# DRIVER_LED_AFE.net
KiCad netlist of a schematic drawn in Altium Designer
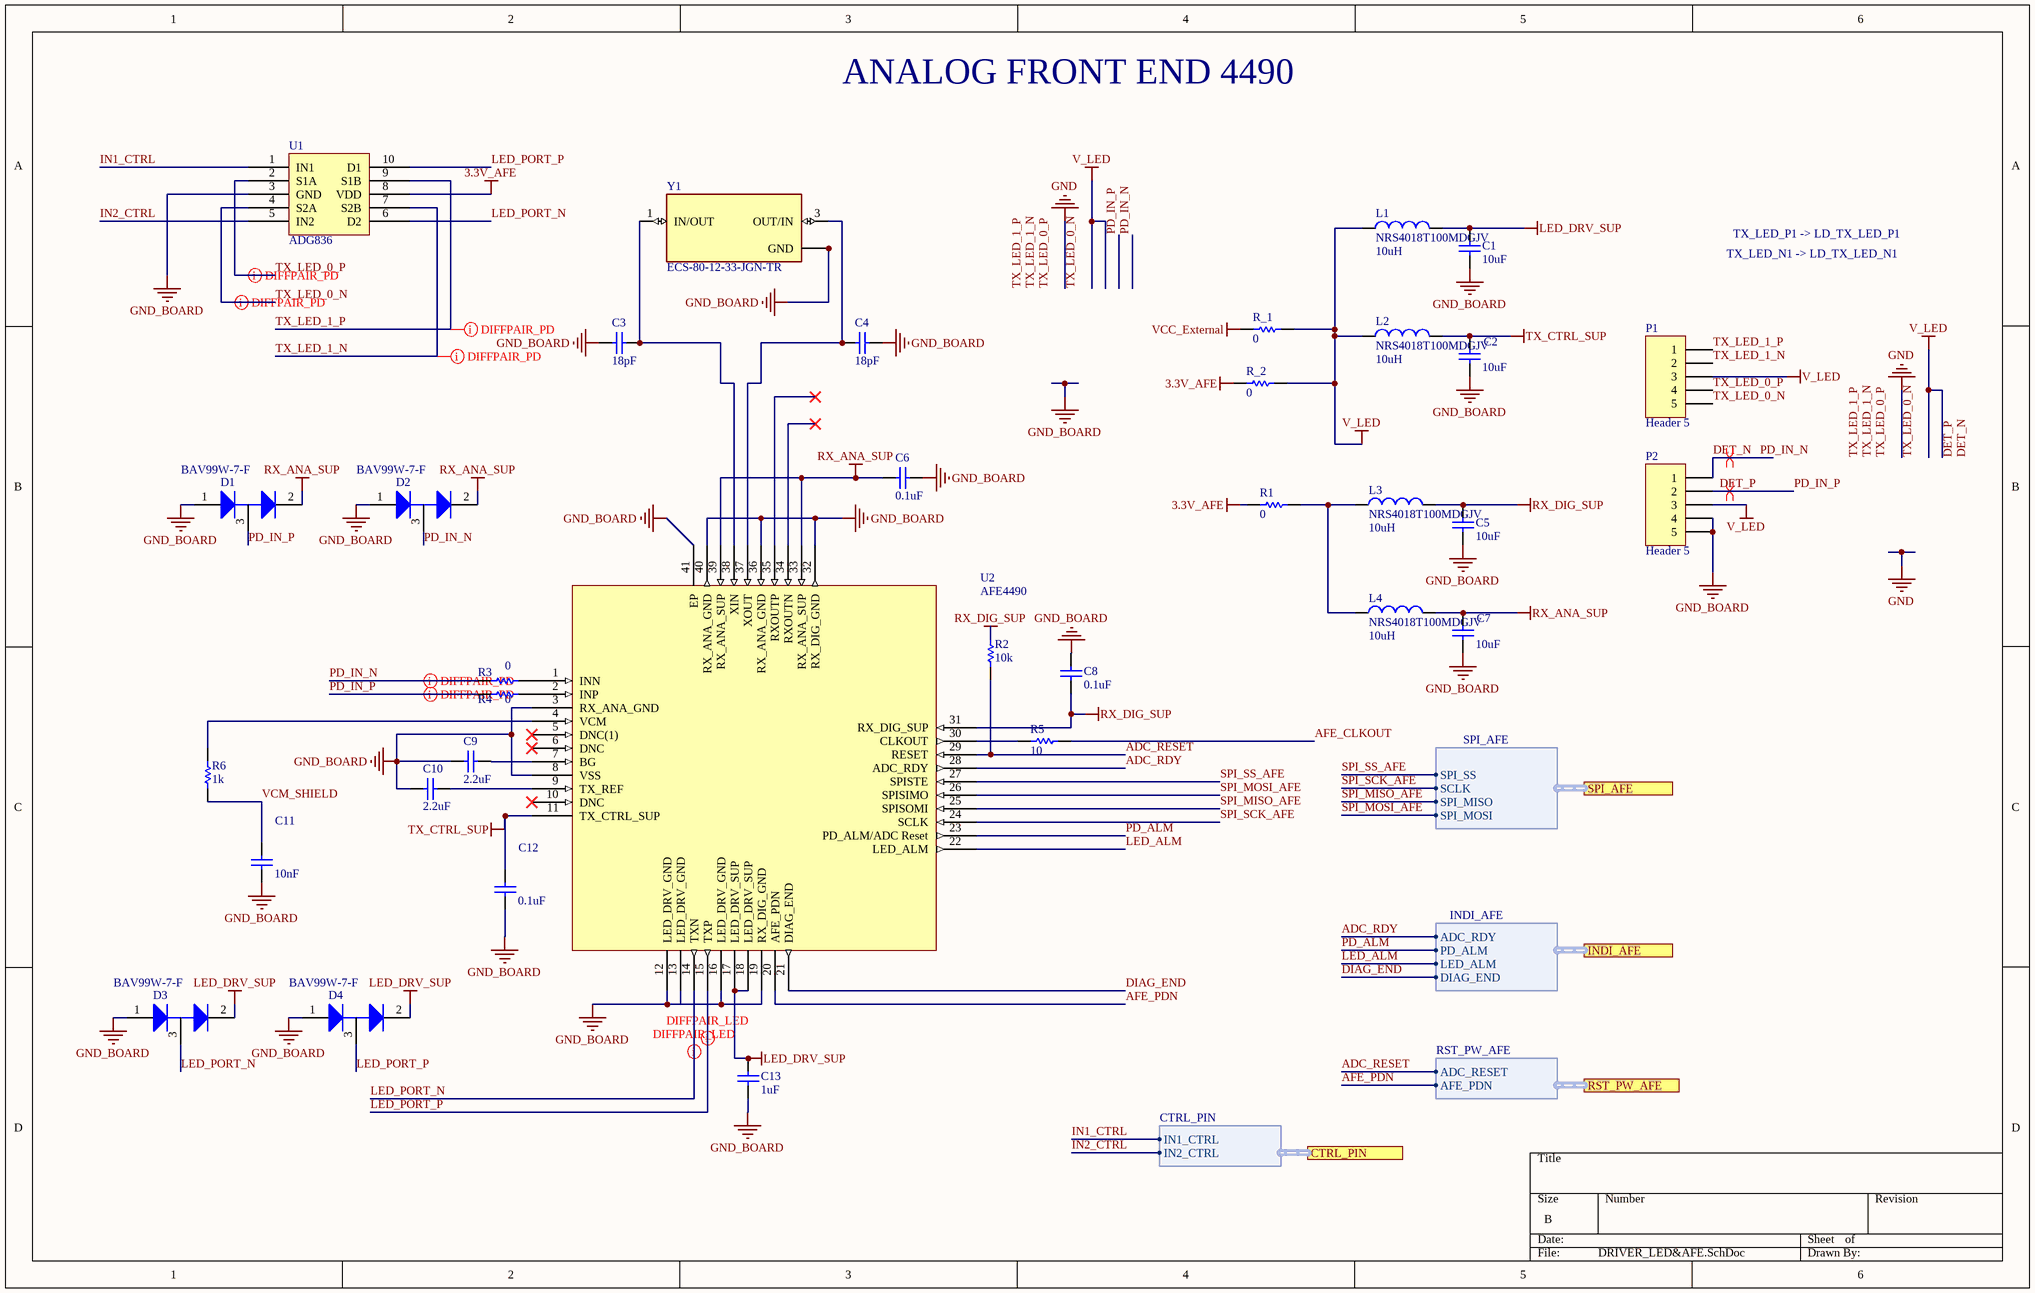
[diagram p0: DRIVER_LED&AFE.SchDoc]

(export (version "E")
  (design (tool "Eeschema 10.0.6"))
  (components
    (comp (ref "C1")
      (value "10uF")
      (footprint "RES-SMD-0603")
      (description "Capacitor")
      (fields (field (name "Comment") "Cap") (field (name "PUBLISHER") "Altium Limited"))
      (libsource (lib "Miscellaneous Devices") (part "Cap"))
    )
    (comp (ref "C2")
      (value "10uF")
      (footprint "RES-SMD-0603")
      (description "Capacitor")
      (fields (field (name "Comment") "Cap") (field (name "PUBLISHER") "Altium Limited"))
      (libsource (lib "Miscellaneous Devices") (part "Cap"))
    )
    (comp (ref "C3")
      (value "18pF")
      (footprint "RES-SMD-0603")
      (description "Capacitor")
      (fields (field (name "Comment") "Cap") (field (name "PUBLISHER") "Altium Limited"))
      (libsource (lib "Miscellaneous Devices") (part "Cap"))
    )
    (comp (ref "C4")
      (value "18pF")
      (footprint "RES-SMD-0603")
      (description "Capacitor")
      (fields (field (name "Comment") "Cap") (field (name "PUBLISHER") "Altium Limited"))
      (libsource (lib "Miscellaneous Devices") (part "Cap"))
    )
    (comp (ref "C5")
      (value "10uF")
      (footprint "RES-SMD-0603")
      (description "Capacitor")
      (fields (field (name "Comment") "Cap") (field (name "PUBLISHER") "Altium Limited"))
      (libsource (lib "Miscellaneous Devices") (part "Cap"))
    )
    (comp (ref "C6")
      (value "0.1uF")
      (footprint "RES-SMD-0603")
      (description "Capacitor")
      (fields (field (name "Comment") "Cap") (field (name "PUBLISHER") "Altium Limited"))
      (libsource (lib "Miscellaneous Devices") (part "Cap"))
    )
    (comp (ref "C7")
      (value "10uF")
      (footprint "RES-SMD-0603")
      (description "Capacitor")
      (fields (field (name "Comment") "Cap") (field (name "PUBLISHER") "Altium Limited"))
      (libsource (lib "Miscellaneous Devices") (part "Cap"))
    )
    (comp (ref "C8")
      (value "0.1uF")
      (footprint "RES-SMD-0603")
      (description "Capacitor")
      (fields (field (name "Comment") "Cap") (field (name "PUBLISHER") "Altium Limited"))
      (libsource (lib "Miscellaneous Devices") (part "Cap"))
    )
    (comp (ref "C9")
      (value "2.2uF")
      (footprint "RES-SMD-0603")
      (description "Capacitor")
      (fields (field (name "Comment") "Cap") (field (name "PUBLISHER") "Altium Limited"))
      (libsource (lib "Miscellaneous Devices") (part "Cap"))
    )
    (comp (ref "C10")
      (value "2.2uF")
      (footprint "RES-SMD-0603")
      (description "Capacitor")
      (fields (field (name "Comment") "Cap") (field (name "PUBLISHER") "Altium Limited"))
      (libsource (lib "Miscellaneous Devices") (part "Cap"))
    )
    (comp (ref "C11")
      (value "10nF")
      (footprint "RES-SMD-0603")
      (description "Capacitor")
      (fields (field (name "Comment") "Cap") (field (name "PUBLISHER") "Altium Limited"))
      (libsource (lib "Miscellaneous Devices") (part "Cap"))
    )
    (comp (ref "C12")
      (value "0.1uF")
      (footprint "RES-SMD-0603")
      (description "Capacitor")
      (fields (field (name "Comment") "Cap") (field (name "PUBLISHER") "Altium Limited"))
      (libsource (lib "Miscellaneous Devices") (part "Cap"))
    )
    (comp (ref "C13")
      (value "1uF")
      (footprint "RES-SMD-0603")
      (description "Capacitor")
      (fields (field (name "Comment") "Cap") (field (name "PUBLISHER") "Altium Limited"))
      (libsource (lib "Miscellaneous Devices") (part "Cap"))
    )
    (comp (ref "D1")
      (value "BAV99W-7-F")
      (footprint "SOT-323")
      (libsource (lib "SF_lib") (part "BAV99W-7-F"))
    )
    (comp (ref "D2")
      (value "BAV99W-7-F")
      (footprint "SOT-323")
      (libsource (lib "SF_lib") (part "BAV99W-7-F"))
    )
    (comp (ref "D3")
      (value "BAV99W-7-F")
      (footprint "SOT-323")
      (libsource (lib "SF_lib") (part "BAV99W-7-F"))
    )
    (comp (ref "D4")
      (value "BAV99W-7-F")
      (footprint "SOT-323")
      (libsource (lib "SF_lib") (part "BAV99W-7-F"))
    )
    (comp (ref "L1")
      (value "NRS4018T100MDGJV")
      (footprint "NRS4018")
      (description "Inductor")
      (fields (field (name "ALTIUM_VALUE") "10uH") (field (name "PUBLISHER") "Altium Limited"))
      (libsource (lib "Miscellaneous Devices") (part "Inductor"))
    )
    (comp (ref "L2")
      (value "NRS4018T100MDGJV")
      (footprint "NRS4018")
      (description "Inductor")
      (fields (field (name "ALTIUM_VALUE") "10uH") (field (name "PUBLISHER") "Altium Limited"))
      (libsource (lib "Miscellaneous Devices") (part "Inductor"))
    )
    (comp (ref "L3")
      (value "NRS4018T100MDGJV")
      (footprint "NRS4018")
      (description "Inductor")
      (fields (field (name "ALTIUM_VALUE") "10uH") (field (name "PUBLISHER") "Altium Limited"))
      (libsource (lib "Miscellaneous Devices") (part "Inductor"))
    )
    (comp (ref "L4")
      (value "NRS4018T100MDGJV")
      (footprint "NRS4018")
      (description "Inductor")
      (fields (field (name "ALTIUM_VALUE") "10uH") (field (name "PUBLISHER") "Altium Limited"))
      (libsource (lib "Miscellaneous Devices") (part "Inductor"))
    )
    (comp (ref "P1")
      (value "Header 5")
      (footprint "HDR1X5")
      (description "Header, 5-Pin")
      (fields (field (name "PUBLISHER") "Altium Limited"))
      (libsource (lib "Miscellaneous Connectors") (part "Header 5"))
    )
    (comp (ref "P2")
      (value "Header 5")
      (footprint "HDR1X5")
      (description "Header, 5-Pin")
      (fields (field (name "PUBLISHER") "Altium Limited"))
      (libsource (lib "Miscellaneous Connectors") (part "Header 5"))
    )
    (comp (ref "R1")
      (value "0")
      (footprint "RES-SMD-0603")
      (description "Resistor")
      (fields (field (name "Comment") "Res1") (field (name "PUBLISHER") "Altium Limited"))
      (libsource (lib "Miscellaneous Devices") (part "Res1"))
    )
    (comp (ref "R2")
      (value "10k")
      (footprint "RES-SMD-0603")
      (description "Resistor")
      (fields (field (name "Comment") "Res1") (field (name "PUBLISHER") "Altium Limited"))
      (libsource (lib "Miscellaneous Devices") (part "Res1"))
    )
    (comp (ref "R3")
      (value "0")
      (footprint "RES-SMD-0603")
      (description "Resistor")
      (fields (field (name "Comment") "Res1") (field (name "PUBLISHER") "Altium Limited"))
      (libsource (lib "Miscellaneous Devices") (part "Res1"))
    )
    (comp (ref "R4")
      (value "0")
      (footprint "RES-SMD-0603")
      (description "Resistor")
      (fields (field (name "Comment") "Res1") (field (name "PUBLISHER") "Altium Limited"))
      (libsource (lib "Miscellaneous Devices") (part "Res1"))
    )
    (comp (ref "R5")
      (value "10")
      (footprint "RES-SMD-0603")
      (description "Resistor")
      (fields (field (name "Comment") "Res1") (field (name "PUBLISHER") "Altium Limited"))
      (libsource (lib "Miscellaneous Devices") (part "Res1"))
    )
    (comp (ref "R6")
      (value "1k")
      (footprint "RES-SMD-0603")
      (description "Resistor")
      (fields (field (name "Comment") "Res1") (field (name "PUBLISHER") "Altium Limited"))
      (libsource (lib "Miscellaneous Devices") (part "Res1"))
    )
    (comp (ref "R_1")
      (value "0")
      (footprint "RES-SMD-0603")
      (description "Resistor")
      (fields (field (name "Comment") "Res1") (field (name "PUBLISHER") "Altium Limited"))
      (libsource (lib "Miscellaneous Devices") (part "Res1"))
    )
    (comp (ref "R_2")
      (value "0")
      (footprint "RES-SMD-0603")
      (description "Resistor")
      (fields (field (name "Comment") "Res1") (field (name "PUBLISHER") "Altium Limited"))
      (libsource (lib "Miscellaneous Devices") (part "Res1"))
    )
    (comp (ref "U1") (value "ADG836") (footprint "MSOP-10") (libsource (lib "SF_lib") (part "ADG836")))
    (comp (ref "U2") (value "AFE4490") (footprint "VQFN (40)") (libsource (lib "SF_lib") (part "AFE4490")))
    (comp (ref "Y1")
      (value "ECS-80-12-33-JGN-TR")
      (footprint "XTAL_ECS-240-8-33-AGN-TR")
      (description "8MHz Â±20ppm Crystal 12pF 400 Ohms 4-SMD, No Lead")
      (fields
        (field (name "MF") "ECS Inc.")
        (field (name "BUYPART") "https://www.snapeda.com/parts/ECS-80-12-33-JGN-TR/ECS%20Inc./view-part/4477300/?ref=eda")
      )
      (libsource (lib "ECS-80-12-33-JGN-TR") (part "ECS-80-12-33-JGN-TR"))
    )
  )
  (nets
    (net (code "5") (name "/ADC_RDY") (class "Default")
      (node (ref "U2") (pin "28") (pinfunction "ADC_RDY_28") (pintype "output"))
    )
    (net (code "6") (name "/ADC_RESET") (class "Default")
      (node (ref "R2") (pin "2") (pinfunction "2_2") (pintype "passive"))
      (node (ref "U2") (pin "29") (pinfunction "RESET_29") (pintype "input"))
    )
    (net (code "7") (name "/AFE_CLKOUT") (class "Default")
      (node (ref "R5") (pin "1") (pinfunction "1_1") (pintype "passive"))
    )
    (net (code "8") (name "/AFE_PDN") (class "Default")
      (node (ref "U2") (pin "20") (pinfunction "AFE_PDN_20") (pintype "passive"))
    )
    (net (code "9") (name "/DET_N") (class "Default")
      (node (ref "D2") (pin "3") (pintype "passive"))
      (node (ref "P2") (pin "1") (pinfunction "1_1") (pintype "passive"))
      (node (ref "R3") (pin "1") (pinfunction "1_1") (pintype "passive"))
    )
    (net (code "10") (name "/DET_P") (class "Default")
      (node (ref "D1") (pin "3") (pintype "passive"))
      (node (ref "P2") (pin "2") (pinfunction "2_2") (pintype "passive"))
      (node (ref "R4") (pin "1") (pinfunction "1_1") (pintype "passive"))
    )
    (net (code "11") (name "/DIAG_END") (class "Default")
      (node (ref "U2") (pin "21") (pinfunction "DIAG_END_21") (pintype "output"))
    )
    (net (code "12") (name "/IN1_CTRL") (class "Default")
      (node (ref "U1") (pin "1") (pinfunction "IN1_1") (pintype "passive"))
    )
    (net (code "13") (name "/IN2_CTRL") (class "Default")
      (node (ref "U1") (pin "5") (pinfunction "IN2_5") (pintype "passive"))
    )
    (net (code "14") (name "/LED_ALM") (class "Default")
      (node (ref "U2") (pin "22") (pinfunction "LED_ALM_22") (pintype "output"))
    )
    (net (code "15") (name "/LED_PORT_N") (class "Default")
      (node (ref "D3") (pin "3") (pintype "passive"))
      (node (ref "U1") (pin "6") (pinfunction "D2_6") (pintype "passive"))
      (node (ref "U2") (pin "14") (pinfunction "TXN_14") (pintype "output"))
    )
    (net (code "16") (name "/LED_PORT_P") (class "Default")
      (node (ref "D4") (pin "3") (pintype "passive"))
      (node (ref "U1") (pin "10") (pinfunction "D1_10") (pintype "passive"))
      (node (ref "U2") (pin "15") (pinfunction "TXP_15") (pintype "output"))
    )
    (net (code "17") (name "/PD_ALM") (class "Default")
      (node (ref "U2") (pin "23") (pinfunction "PD_ALM/ADC_Reset_23") (pintype "output"))
    )
    (net (code "18") (name "/SPI_MISO_AFE") (class "Default")
      (node (ref "U2") (pin "25") (pinfunction "SPISOMI_25") (pintype "input"))
    )
    (net (code "19") (name "/SPI_MOSI_AFE") (class "Default")
      (node (ref "U2") (pin "26") (pinfunction "SPISIMO_26") (pintype "input"))
    )
    (net (code "20") (name "/SPI_SCK_AFE") (class "Default")
      (node (ref "U2") (pin "24") (pinfunction "SCLK_24") (pintype "input"))
    )
    (net (code "21") (name "/SPI_SS_AFE") (class "Default")
      (node (ref "U2") (pin "27") (pinfunction "SPISTE_27") (pintype "input"))
    )
    (net (code "22") (name "/TX_LED_0_N") (class "Default")
      (node (ref "P1") (pin "5") (pinfunction "5_5") (pintype "passive"))
      (node (ref "U1") (pin "4") (pinfunction "S2A_4") (pintype "passive"))
    )
    (net (code "23") (name "/TX_LED_0_P") (class "Default")
      (node (ref "P1") (pin "4") (pinfunction "4_4") (pintype "passive"))
      (node (ref "U1") (pin "2") (pinfunction "S1A_2") (pintype "passive"))
    )
    (net (code "24") (name "/TX_LED_1_N") (class "Default")
      (node (ref "P1") (pin "2") (pinfunction "2_2") (pintype "passive"))
      (node (ref "U1") (pin "7") (pinfunction "S2B_7") (pintype "passive"))
    )
    (net (code "25") (name "/TX_LED_1_P") (class "Default")
      (node (ref "P1") (pin "1") (pinfunction "1_1") (pintype "passive"))
      (node (ref "U1") (pin "9") (pinfunction "S1B_9") (pintype "passive"))
    )
    (net (code "26") (name "/VCM_SHIELD") (class "Default")
      (node (ref "C11") (pin "2") (pinfunction "2_2") (pintype "passive"))
      (node (ref "R6") (pin "2") (pinfunction "2_2") (pintype "passive"))
    )
    (net (code "31") (name "3.3V_AFE") (class "Default")
      (node (ref "R1") (pin "1") (pinfunction "1_1") (pintype "passive"))
      (node (ref "R_2") (pin "1") (pinfunction "1_1") (pintype "passive"))
      (node (ref "U1") (pin "8") (pinfunction "VDD_8") (pintype "passive"))
    )
    (net (code "33") (name "GND_BOARD") (class "Default")
      (node (ref "C1") (pin "2") (pinfunction "2_2") (pintype "passive"))
      (node (ref "C10") (pin "2") (pinfunction "2_2") (pintype "passive"))
      (node (ref "C11") (pin "1") (pinfunction "1_1") (pintype "passive"))
      (node (ref "C12") (pin "1") (pinfunction "1_1") (pintype "passive"))
      (node (ref "C13") (pin "1") (pinfunction "1_1") (pintype "passive"))
      (node (ref "C2") (pin "1") (pinfunction "1_1") (pintype "passive"))
      (node (ref "C3") (pin "1") (pinfunction "1_1") (pintype "passive"))
      (node (ref "C4") (pin "2") (pinfunction "2_2") (pintype "passive"))
      (node (ref "C5") (pin "2") (pinfunction "2_2") (pintype "passive"))
      (node (ref "C6") (pin "2") (pinfunction "2_2") (pintype "passive"))
      (node (ref "C7") (pin "1") (pinfunction "1_1") (pintype "passive"))
      (node (ref "C8") (pin "1") (pinfunction "1_1") (pintype "passive"))
      (node (ref "C9") (pin "2") (pinfunction "2_2") (pintype "passive"))
      (node (ref "D1") (pin "1") (pintype "passive"))
      (node (ref "D2") (pin "1") (pintype "passive"))
      (node (ref "D3") (pin "1") (pintype "passive"))
      (node (ref "D4") (pin "1") (pintype "passive"))
      (node (ref "P2") (pin "4") (pinfunction "4_4") (pintype "passive"))
      (node (ref "P2") (pin "5") (pinfunction "5_5") (pintype "passive"))
      (node (ref "U1") (pin "3") (pinfunction "GND_3") (pintype "passive"))
      (node (ref "U2") (pin "12") (pinfunction "LED_DRV_GND_12") (pintype "passive"))
      (node (ref "U2") (pin "13") (pinfunction "LED_DRV_GND_13") (pintype "passive"))
      (node (ref "U2") (pin "16") (pinfunction "LED_DRV_GND_16") (pintype "passive"))
      (node (ref "U2") (pin "19") (pinfunction "RX_DIG_GND_19") (pintype "passive"))
      (node (ref "U2") (pin "3") (pinfunction "RX_ANA_GND_3") (pintype "passive"))
      (node (ref "U2") (pin "32") (pinfunction "RX_DIG_GND_32") (pintype "output"))
      (node (ref "U2") (pin "36") (pinfunction "RX_ANA_GND_36") (pintype "input"))
      (node (ref "U2") (pin "40") (pinfunction "RX_ANA_GND_40") (pintype "output"))
      (node (ref "U2") (pin "41") (pinfunction "EP_41") (pintype "passive"))
      (node (ref "U2") (pin "8") (pinfunction "VSS_8") (pintype "passive"))
      (node (ref "Y1") (pin "2") (pinfunction "GND_2") (pintype "power_in"))
      (node (ref "Y1") (pin "4") (pinfunction "GND_4") (pintype "power_in"))
    )
    (net (code "34") (name "LED_DRV_SUP") (class "Default")
      (node (ref "C1") (pin "1") (pinfunction "1_1") (pintype "passive"))
      (node (ref "C13") (pin "2") (pinfunction "2_2") (pintype "passive"))
      (node (ref "D3") (pin "2") (pintype "passive"))
      (node (ref "D4") (pin "2") (pintype "passive"))
      (node (ref "L1") (pin "2") (pinfunction "2_2") (pintype "passive"))
      (node (ref "U2") (pin "17") (pinfunction "LED_DRV_SUP_17") (pintype "passive"))
      (node (ref "U2") (pin "18") (pinfunction "LED_DRV_SUP_18") (pintype "passive"))
    )
    (net (code "35") (name "Net-(L3-Pad1)") (class "Default")
      (node (ref "L3") (pin "1") (pinfunction "1_1") (pintype "passive"))
      (node (ref "L4") (pin "1") (pinfunction "1_1") (pintype "passive"))
      (node (ref "R1") (pin "2") (pinfunction "2_2") (pintype "passive"))
    )
    (net (code "36") (name "Net-(U2-BG)") (class "Default")
      (node (ref "C9") (pin "1") (pinfunction "1_1") (pintype "passive"))
      (node (ref "U2") (pin "7") (pinfunction "BG_7") (pintype "input"))
    )
    (net (code "37") (name "Net-(U2-CLKOUT)") (class "Default")
      (node (ref "R5") (pin "2") (pinfunction "2_2") (pintype "passive"))
      (node (ref "U2") (pin "30") (pinfunction "CLKOUT_30") (pintype "output"))
    )
    (net (code "38") (name "Net-(U2-INN)") (class "Default")
      (node (ref "R3") (pin "2") (pinfunction "2_2") (pintype "passive"))
      (node (ref "U2") (pin "1") (pinfunction "INN_1") (pintype "input"))
    )
    (net (code "39") (name "Net-(U2-INP)") (class "Default")
      (node (ref "R4") (pin "2") (pinfunction "2_2") (pintype "passive"))
      (node (ref "U2") (pin "2") (pinfunction "INP_2") (pintype "input"))
    )
    (net (code "40") (name "Net-(U2-TX_REF)") (class "Default")
      (node (ref "C10") (pin "1") (pinfunction "1_1") (pintype "passive"))
      (node (ref "U2") (pin "9") (pinfunction "TX_REF_9") (pintype "input"))
    )
    (net (code "41") (name "Net-(U2-VCM)") (class "Default")
      (node (ref "R6") (pin "1") (pinfunction "1_1") (pintype "passive"))
      (node (ref "U2") (pin "4") (pinfunction "VCM_4") (pintype "input"))
    )
    (net (code "42") (name "Net-(U2-XIN)") (class "Default")
      (node (ref "C3") (pin "2") (pinfunction "2_2") (pintype "passive"))
      (node (ref "U2") (pin "38") (pinfunction "XIN_38") (pintype "input"))
      (node (ref "Y1") (pin "1") (pinfunction "IN/OUT_1") (pintype "bidirectional"))
    )
    (net (code "43") (name "Net-(U2-XOUT)") (class "Default")
      (node (ref "C4") (pin "1") (pinfunction "1_1") (pintype "passive"))
      (node (ref "U2") (pin "37") (pinfunction "XOUT_37") (pintype "input"))
      (node (ref "Y1") (pin "3") (pinfunction "OUT/IN_3") (pintype "bidirectional"))
    )
    (net (code "44") (name "RX_ANA_SUP") (class "Default")
      (node (ref "C6") (pin "1") (pinfunction "1_1") (pintype "passive"))
      (node (ref "C7") (pin "2") (pinfunction "2_2") (pintype "passive"))
      (node (ref "D1") (pin "2") (pintype "passive"))
      (node (ref "D2") (pin "2") (pintype "passive"))
      (node (ref "L4") (pin "2") (pinfunction "2_2") (pintype "passive"))
      (node (ref "U2") (pin "33") (pinfunction "RX_ANA_SUP_33") (pintype "input"))
      (node (ref "U2") (pin "39") (pinfunction "RX_ANA_SUP_39") (pintype "input"))
    )
    (net (code "45") (name "RX_DIG_SUP") (class "Default")
      (node (ref "C5") (pin "1") (pinfunction "1_1") (pintype "passive"))
      (node (ref "C8") (pin "2") (pinfunction "2_2") (pintype "passive"))
      (node (ref "L3") (pin "2") (pinfunction "2_2") (pintype "passive"))
      (node (ref "R2") (pin "1") (pinfunction "1_1") (pintype "passive"))
      (node (ref "U2") (pin "31") (pinfunction "RX_DIG_SUP_31") (pintype "input"))
    )
    (net (code "46") (name "TX_CTRL_SUP") (class "Default")
      (node (ref "C12") (pin "2") (pinfunction "2_2") (pintype "passive"))
      (node (ref "C2") (pin "2") (pinfunction "2_2") (pintype "passive"))
      (node (ref "L2") (pin "2") (pinfunction "2_2") (pintype "passive"))
      (node (ref "U2") (pin "11") (pinfunction "TX_CTRL_SUP_11") (pintype "passive"))
    )
    (net (code "47") (name "VCC_External") (class "Default")
      (node (ref "R_1") (pin "1") (pinfunction "1_1") (pintype "passive"))
    )
    (net (code "48") (name "V_LED") (class "Default")
      (node (ref "L1") (pin "1") (pinfunction "1_1") (pintype "passive"))
      (node (ref "L2") (pin "1") (pinfunction "1_1") (pintype "passive"))
      (node (ref "P1") (pin "3") (pinfunction "3_3") (pintype "passive"))
      (node (ref "P2") (pin "3") (pinfunction "3_3") (pintype "passive"))
      (node (ref "R_1") (pin "2") (pinfunction "2_2") (pintype "passive"))
      (node (ref "R_2") (pin "2") (pinfunction "2_2") (pintype "passive"))
    )
    (net (code "49") (name "unconnected-(U2-DNC(1)-Pad5)") (class "Default")
      (node (ref "U2") (pin "5") (pinfunction "DNC(1)_5") (pintype "input+no_connect"))
    )
    (net (code "50") (name "unconnected-(U2-DNC-Pad6)") (class "Default")
      (node (ref "U2") (pin "6") (pinfunction "DNC_6") (pintype "input+no_connect"))
    )
    (net (code "51") (name "unconnected-(U2-DNC-Pad10)") (class "Default")
      (node (ref "U2") (pin "10") (pinfunction "DNC_10") (pintype "input+no_connect"))
    )
    (net (code "52") (name "unconnected-(U2-RXOUTN-Pad34)") (class "Default")
      (node (ref "U2") (pin "34") (pinfunction "RXOUTN_34") (pintype "input+no_connect"))
    )
    (net (code "53") (name "unconnected-(U2-RXOUTP-Pad35)") (class "Default")
      (node (ref "U2") (pin "35") (pinfunction "RXOUTP_35") (pintype "input+no_connect"))
    )
  )
)
